# I2CBuff.net
KiCad netlist of a schematic drawn in EAGLE
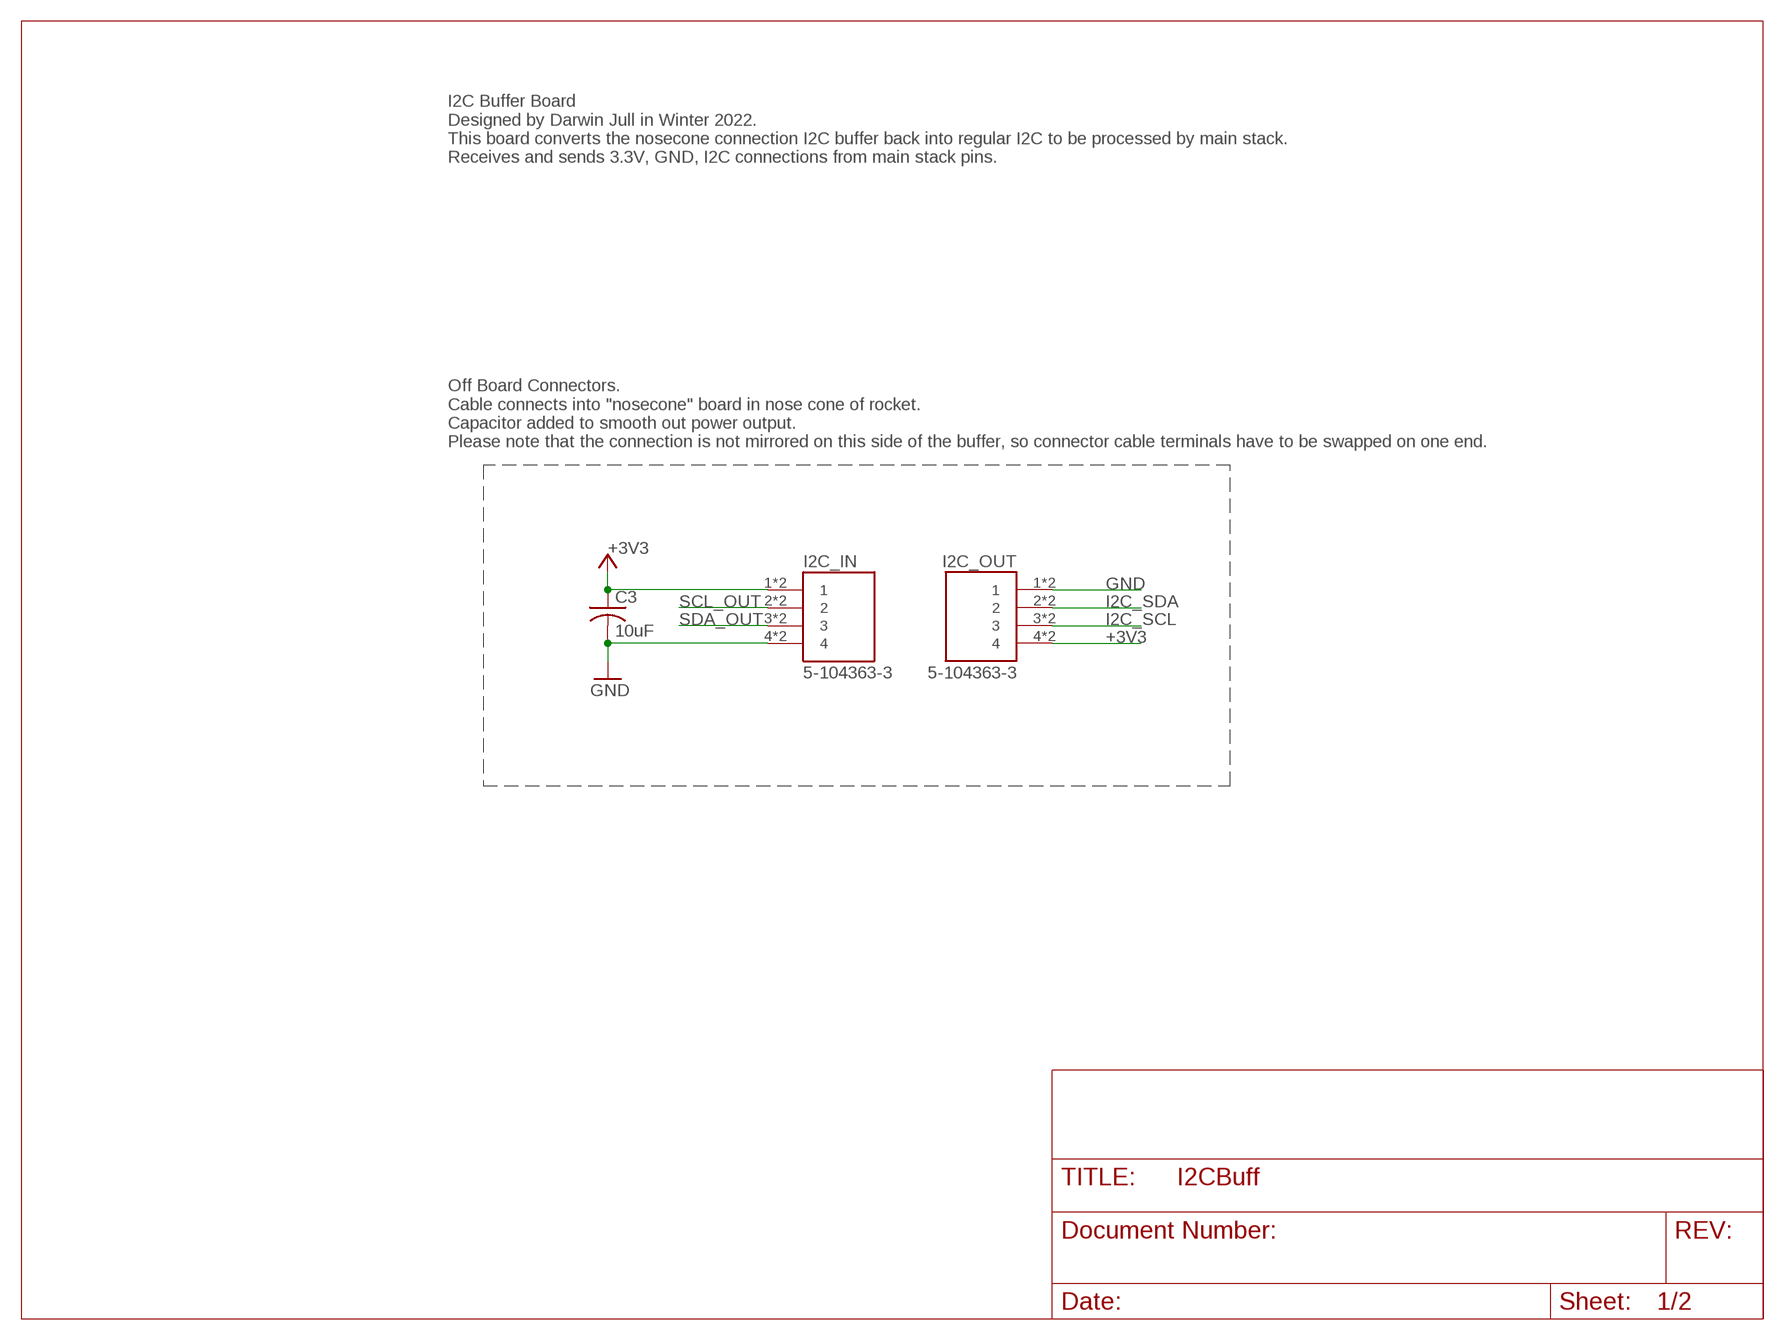
[diagram p0: schematic, sheet 1]
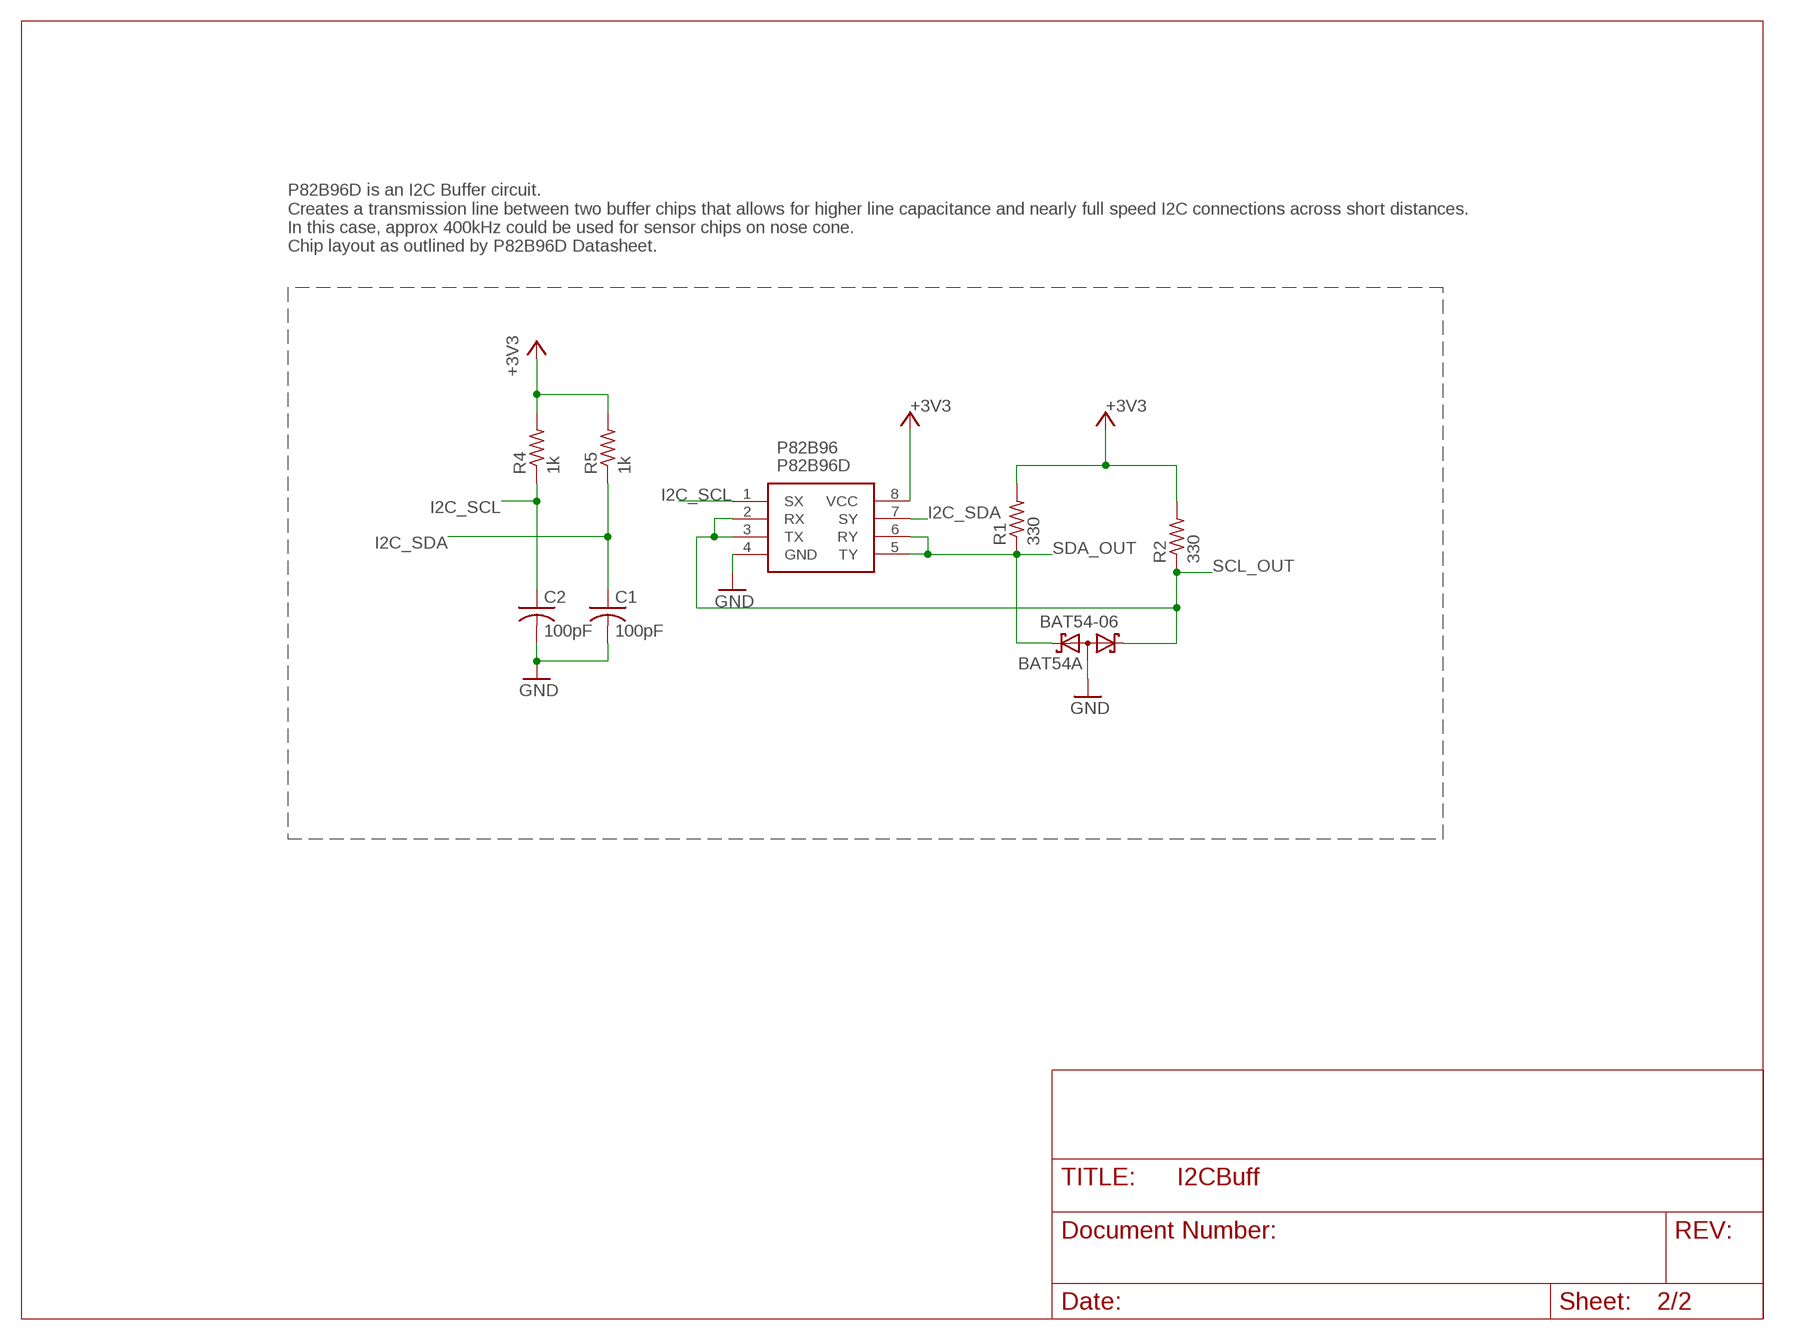
[diagram p1: schematic, sheet 2]

(export (version "E")
  (design (tool "Eeschema 10.0.6"))
  (components
    (comp (ref "C3")
      (value "10uF")
      (footprint "eagle-import:C0805")
      (libsource (lib "eagle-import") (part "C-USC0805"))
    )
    (comp (ref "I2C_IN")
      (value "5-104363-3")
      (footprint "eagle-import:TE_5-104363-3")
      (fields
        (field (name "DIGI-KEY_PART_NUMBER") "A32565-ND")
        (field (name "MF") "TE Connectivity")
        (field (name "MP") "51043633")
      )
      (libsource (lib "eagle-import") (part "5-104363-3"))
    )
    (comp (ref "I2C_OUT")
      (value "5-104363-3")
      (footprint "eagle-import:TE_5-104363-3")
      (fields
        (field (name "DIGI-KEY_PART_NUMBER") "A32565-ND")
        (field (name "MF") "TE Connectivity")
        (field (name "MP") "51043633")
      )
      (libsource (lib "eagle-import") (part "5-104363-3"))
    )
    (comp (ref "C1")
      (value "100pF")
      (footprint "eagle-import:C0805")
      (libsource (lib "eagle-import") (part "C-USC0805"))
    )
    (comp (ref "C2")
      (value "100pF")
      (footprint "eagle-import:C0805")
      (libsource (lib "eagle-import") (part "C-USC0805"))
    )
    (comp (ref "D1")
      (value "BAT54-06")
      (footprint "eagle-import:SOT23")
      (libsource (lib "eagle-import") (part "BAT54-06"))
    )
    (comp (ref "P82B96")
      (value "P82B96D")
      (footprint "eagle-import:SOIC127P600X175-8N")
      (fields (field (name "MOUSER_PART_NUMBER") "595-P82B96D"))
      (libsource (lib "eagle-import") (part "P82B96D"))
    )
    (comp (ref "R1")
      (value "330")
      (footprint "eagle-import:R0805")
      (libsource (lib "eagle-import") (part "R-US_R0805"))
    )
    (comp (ref "R2")
      (value "330")
      (footprint "eagle-import:R0805")
      (libsource (lib "eagle-import") (part "R-US_R0805"))
    )
    (comp (ref "R4")
      (value "1k")
      (footprint "eagle-import:R0805")
      (libsource (lib "eagle-import") (part "R-US_R0805"))
    )
    (comp (ref "R5")
      (value "1k")
      (footprint "eagle-import:R0805")
      (libsource (lib "eagle-import") (part "R-US_R0805"))
    )
  )
  (nets
    (net (code "1") (name "+3V3") (class "Default")
      (node (ref "C3") (pin "1") (pinfunction "1_1") (pintype "passive"))
      (node (ref "I2C_IN") (pin "1") (pinfunction "1_1") (pintype "passive"))
      (node (ref "I2C_IN") (pin "1_1") (pinfunction "1_1_1") (pintype "passive"))
      (node (ref "I2C_OUT") (pin "4") (pinfunction "4_4") (pintype "passive"))
      (node (ref "I2C_OUT") (pin "4_1") (pinfunction "4_4_1") (pintype "passive"))
      (node (ref "P82B96") (pin "8") (pinfunction "VCC_8") (pintype "bidirectional"))
      (node (ref "R1") (pin "2") (pinfunction "2_2") (pintype "passive"))
      (node (ref "R2") (pin "2") (pinfunction "2_2") (pintype "passive"))
      (node (ref "R4") (pin "2") (pinfunction "2_2") (pintype "passive"))
      (node (ref "R5") (pin "2") (pinfunction "2_2") (pintype "passive"))
    )
    (net (code "2") (name "GND") (class "Default")
      (node (ref "C1") (pin "2") (pinfunction "2_2") (pintype "passive"))
      (node (ref "C2") (pin "2") (pinfunction "2_2") (pintype "passive"))
      (node (ref "C3") (pin "2") (pinfunction "2_2") (pintype "passive"))
      (node (ref "D1") (pin "3") (pinfunction "3_3") (pintype "passive"))
      (node (ref "I2C_IN") (pin "4") (pinfunction "4_4") (pintype "passive"))
      (node (ref "I2C_IN") (pin "4_1") (pinfunction "4_4_1") (pintype "passive"))
      (node (ref "I2C_OUT") (pin "1") (pinfunction "1_1") (pintype "passive"))
      (node (ref "I2C_OUT") (pin "1_1") (pinfunction "1_1_1") (pintype "passive"))
      (node (ref "P82B96") (pin "4") (pinfunction "GND_4") (pintype "bidirectional"))
    )
    (net (code "3") (name "I2C_SCL") (class "Default")
      (node (ref "C2") (pin "1") (pinfunction "1_1") (pintype "passive"))
      (node (ref "I2C_OUT") (pin "3") (pinfunction "3_3") (pintype "passive"))
      (node (ref "I2C_OUT") (pin "3_1") (pinfunction "3_3_1") (pintype "passive"))
      (node (ref "P82B96") (pin "1") (pinfunction "SX_1") (pintype "bidirectional"))
      (node (ref "R4") (pin "1") (pinfunction "1_1") (pintype "passive"))
    )
    (net (code "4") (name "I2C_SDA") (class "Default")
      (node (ref "C1") (pin "1") (pinfunction "1_1") (pintype "passive"))
      (node (ref "I2C_OUT") (pin "2") (pinfunction "2_2") (pintype "passive"))
      (node (ref "I2C_OUT") (pin "2_1") (pinfunction "2_2_1") (pintype "passive"))
      (node (ref "P82B96") (pin "7") (pinfunction "SY_7") (pintype "bidirectional"))
      (node (ref "R5") (pin "1") (pinfunction "1_1") (pintype "passive"))
    )
    (net (code "5") (name "SCL_OUT") (class "Default")
      (node (ref "D1") (pin "1") (pinfunction "1_1") (pintype "passive"))
      (node (ref "I2C_IN") (pin "2") (pinfunction "2_2") (pintype "passive"))
      (node (ref "I2C_IN") (pin "2_1") (pinfunction "2_2_1") (pintype "passive"))
      (node (ref "P82B96") (pin "2") (pinfunction "RX_2") (pintype "bidirectional"))
      (node (ref "P82B96") (pin "3") (pinfunction "TX_3") (pintype "bidirectional"))
      (node (ref "R2") (pin "1") (pinfunction "1_1") (pintype "passive"))
    )
    (net (code "6") (name "SDA_OUT") (class "Default")
      (node (ref "D1") (pin "2") (pinfunction "2_2") (pintype "passive"))
      (node (ref "I2C_IN") (pin "3") (pinfunction "3_3") (pintype "passive"))
      (node (ref "I2C_IN") (pin "3_1") (pinfunction "3_3_1") (pintype "passive"))
      (node (ref "P82B96") (pin "5") (pinfunction "TY_5") (pintype "bidirectional"))
      (node (ref "P82B96") (pin "6") (pinfunction "RY_6") (pintype "bidirectional"))
      (node (ref "R1") (pin "1") (pinfunction "1_1") (pintype "passive"))
    )
  )
)
